# SCH_The-Weather-Station_2024-05-15.net
KiCad netlist of a schematic drawn in EasyEDA
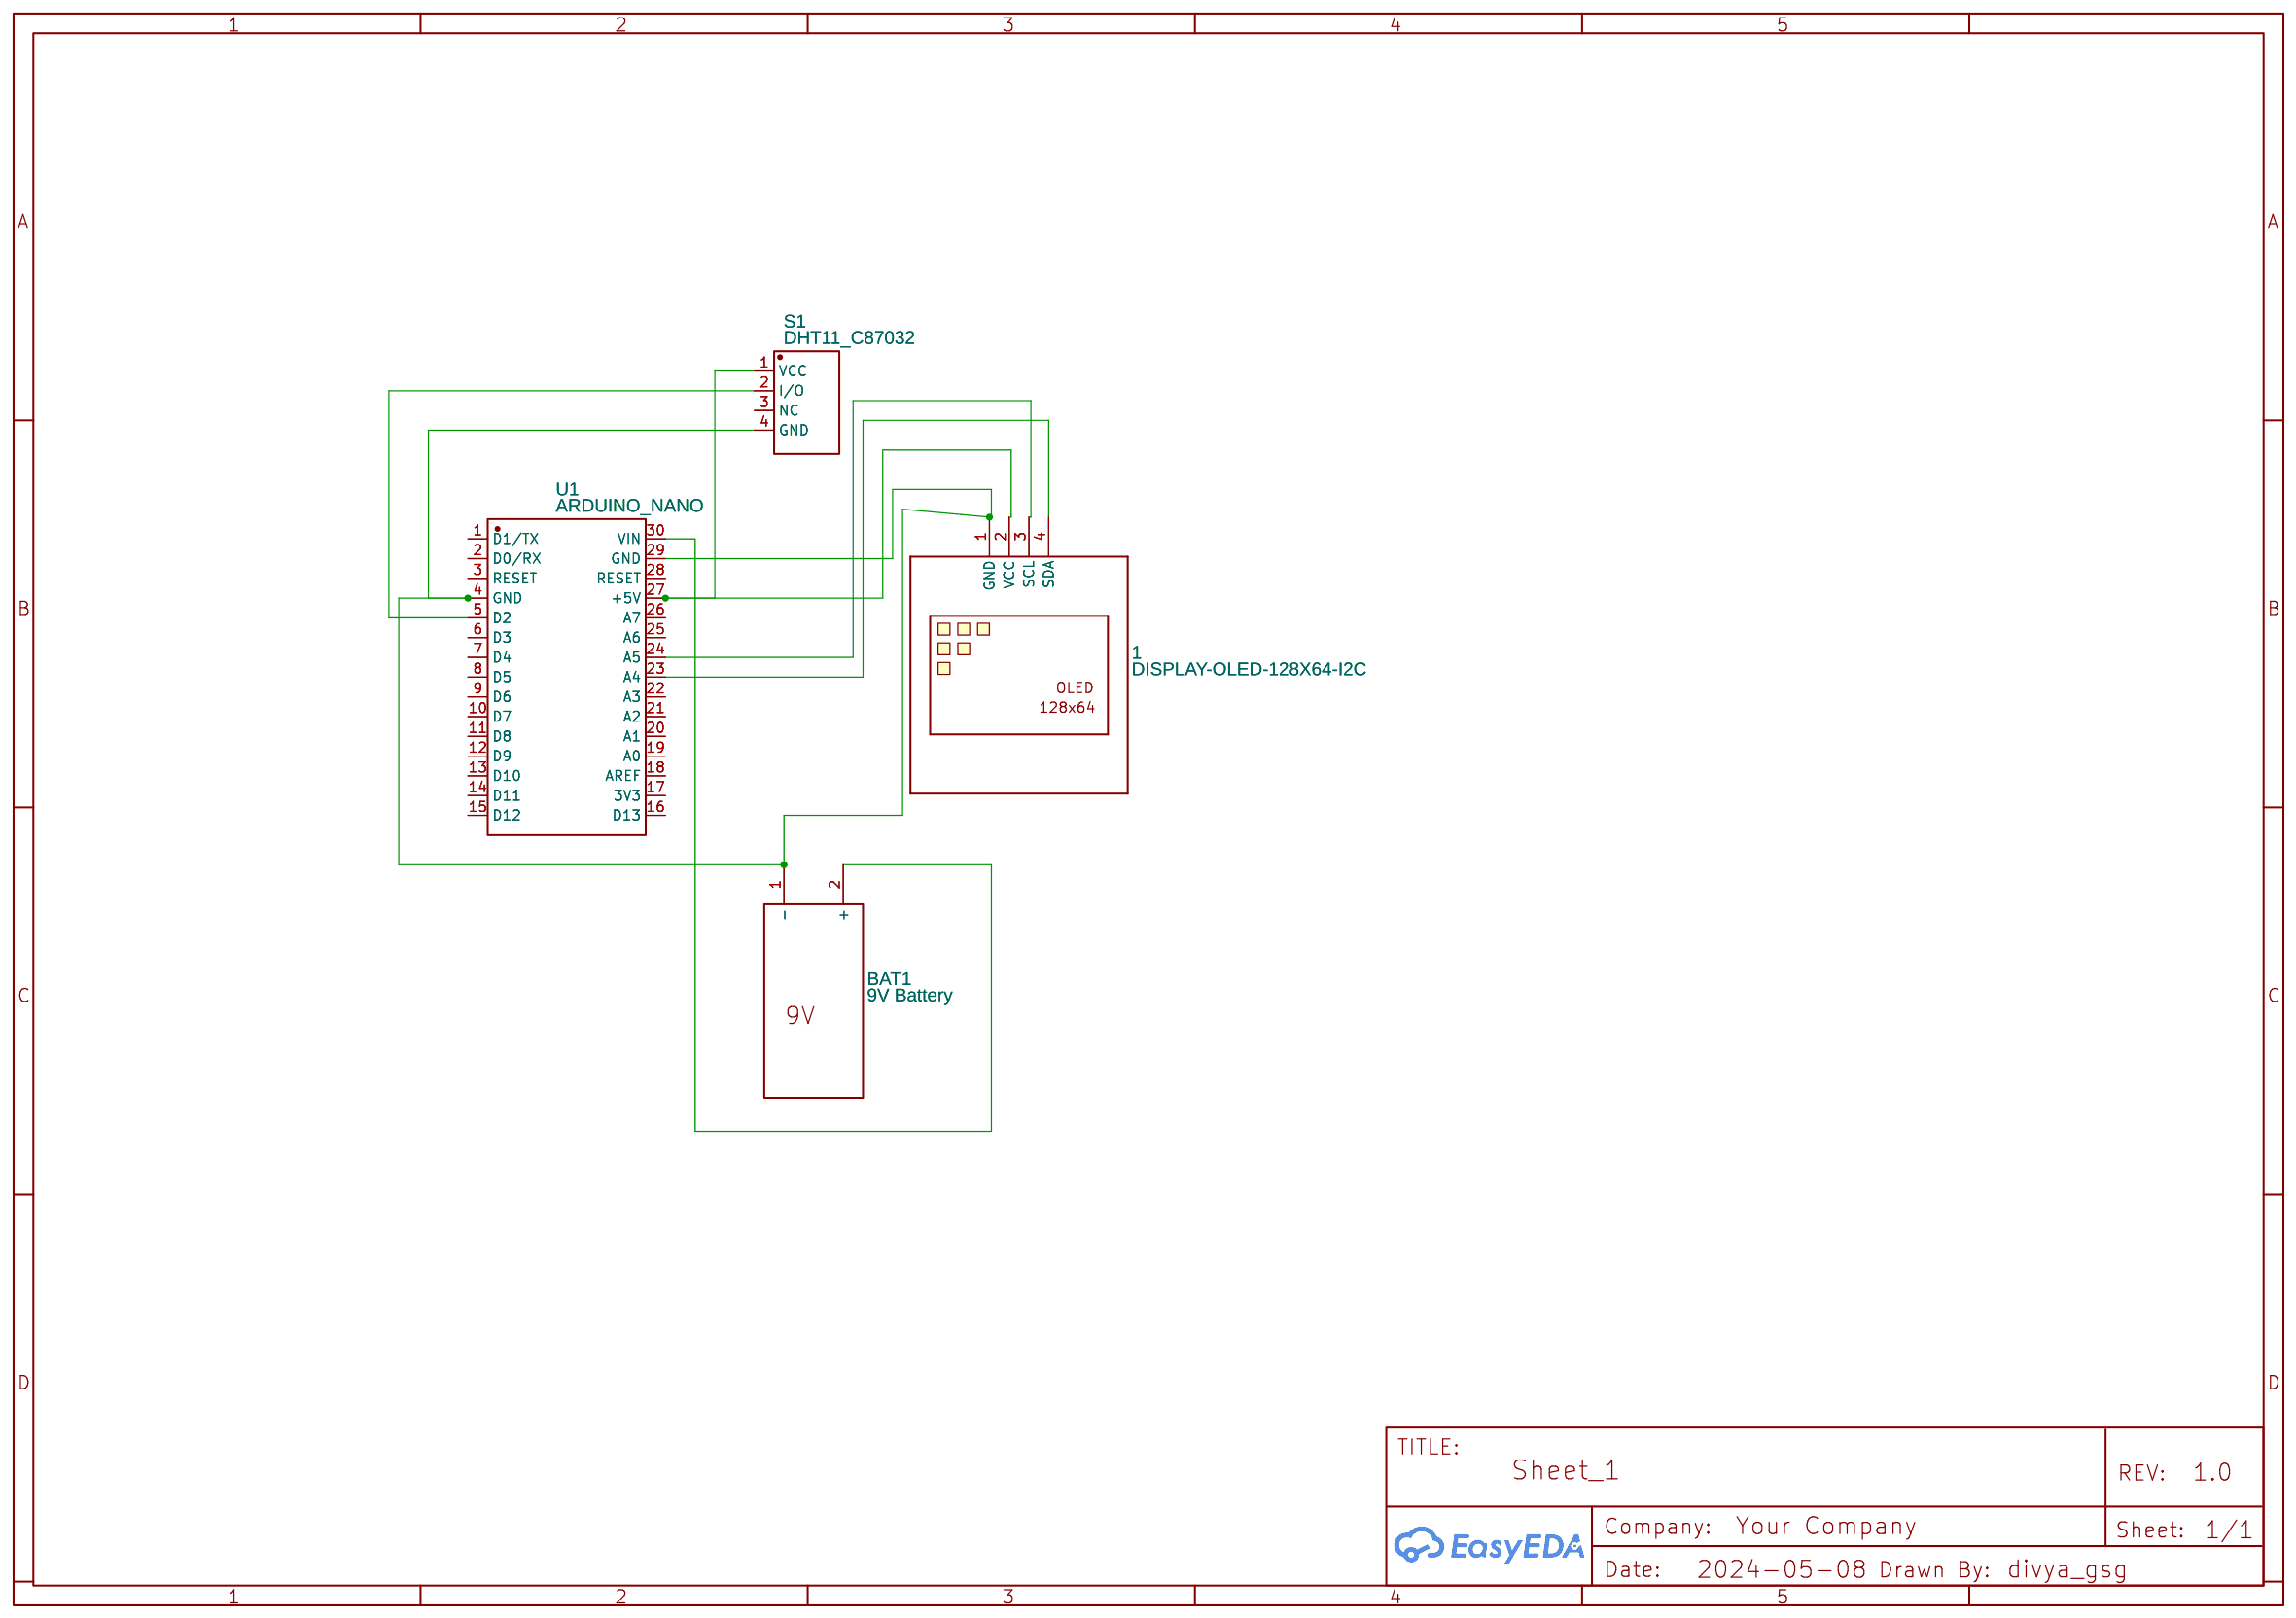
[diagram p0: schematic sheet]

(export (version "E")
  (design (tool "Eeschema 10.0.6"))
  (components
    (comp (ref "1") (value "DISPLAY-OLED-128X64-I2C") (libsource (lib "") (part "DISPLAY-OLED-128X64-I2C")))
    (comp (ref "BAT1") (value "9V Battery") (libsource (lib "") (part "9V Battery")))
    (comp (ref "S1")
      (value "DHT11_C87032")
      (fields (field (name "Manufacturer Part") "DHT11") (field (name "Manufacturer") "AOSONG"))
      (libsource (lib "") (part "DHT11_C87032"))
    )
    (comp (ref "U1") (value "ARDUINO_NANO") (libsource (lib "") (part "ARDUINO_NANO")))
  )
  (nets
    (net (code "1") (name "Net-(1-GND)") (class "Default")
      (node (ref "1") (pin "1") (pinfunction "GND_1") (pintype "bidirectional"))
      (node (ref "BAT1") (pin "1") (pinfunction "-_1") (pintype "unspecified"))
      (node (ref "S1") (pin "4") (pinfunction "GND_4") (pintype "unspecified"))
      (node (ref "U1") (pin "29") (pinfunction "GND_29") (pintype "unspecified"))
      (node (ref "U1") (pin "4") (pinfunction "GND_4") (pintype "unspecified"))
    )
    (net (code "2") (name "Net-(1-SCL)") (class "Default")
      (node (ref "1") (pin "3") (pinfunction "SCL_3") (pintype "bidirectional"))
      (node (ref "U1") (pin "24") (pinfunction "A5_24") (pintype "unspecified"))
    )
    (net (code "3") (name "Net-(1-SDA)") (class "Default")
      (node (ref "1") (pin "4") (pinfunction "SDA_4") (pintype "bidirectional"))
      (node (ref "U1") (pin "23") (pinfunction "A4_23") (pintype "unspecified"))
    )
    (net (code "4") (name "Net-(1-VCC)") (class "Default")
      (node (ref "1") (pin "2") (pinfunction "VCC_2") (pintype "bidirectional"))
      (node (ref "S1") (pin "1") (pinfunction "VCC_1") (pintype "unspecified"))
      (node (ref "U1") (pin "27") (pinfunction "+5V_27") (pintype "unspecified"))
    )
    (net (code "5") (name "Net-(BAT1-+)") (class "Default")
      (node (ref "BAT1") (pin "2") (pinfunction "+_2") (pintype "unspecified"))
      (node (ref "U1") (pin "30") (pinfunction "VIN_30") (pintype "unspecified"))
    )
    (net (code "6") (name "Net-(S1-I{slash}O)") (class "Default")
      (node (ref "S1") (pin "2") (pinfunction "I/O_2") (pintype "unspecified"))
      (node (ref "U1") (pin "5") (pinfunction "D2_5") (pintype "unspecified"))
    )
    (net (code "7") (name "unconnected-(S1-NC-Pad3)") (class "Default")
      (node (ref "S1") (pin "3") (pinfunction "NC_3") (pintype "unspecified"))
    )
    (net (code "8") (name "unconnected-(U1-3V3-Pad17)") (class "Default")
      (node (ref "U1") (pin "17") (pinfunction "3V3_17") (pintype "unspecified"))
    )
    (net (code "9") (name "unconnected-(U1-A0-Pad19)") (class "Default")
      (node (ref "U1") (pin "19") (pinfunction "A0_19") (pintype "unspecified"))
    )
    (net (code "10") (name "unconnected-(U1-A1-Pad20)") (class "Default")
      (node (ref "U1") (pin "20") (pinfunction "A1_20") (pintype "unspecified"))
    )
    (net (code "11") (name "unconnected-(U1-A2-Pad21)") (class "Default")
      (node (ref "U1") (pin "21") (pinfunction "A2_21") (pintype "unspecified"))
    )
    (net (code "12") (name "unconnected-(U1-A3-Pad22)") (class "Default")
      (node (ref "U1") (pin "22") (pinfunction "A3_22") (pintype "unspecified"))
    )
    (net (code "13") (name "unconnected-(U1-A6-Pad25)") (class "Default")
      (node (ref "U1") (pin "25") (pinfunction "A6_25") (pintype "unspecified"))
    )
    (net (code "14") (name "unconnected-(U1-A7-Pad26)") (class "Default")
      (node (ref "U1") (pin "26") (pinfunction "A7_26") (pintype "unspecified"))
    )
    (net (code "15") (name "unconnected-(U1-AREF-Pad18)") (class "Default")
      (node (ref "U1") (pin "18") (pinfunction "AREF_18") (pintype "unspecified"))
    )
    (net (code "16") (name "unconnected-(U1-D0{slash}RX-Pad2)") (class "Default")
      (node (ref "U1") (pin "2") (pinfunction "D0/RX_2") (pintype "unspecified"))
    )
    (net (code "17") (name "unconnected-(U1-D1{slash}TX-Pad1)") (class "Default")
      (node (ref "U1") (pin "1") (pinfunction "D1/TX_1") (pintype "unspecified"))
    )
    (net (code "18") (name "unconnected-(U1-D3-Pad6)") (class "Default")
      (node (ref "U1") (pin "6") (pinfunction "D3_6") (pintype "unspecified"))
    )
    (net (code "19") (name "unconnected-(U1-D4-Pad7)") (class "Default")
      (node (ref "U1") (pin "7") (pinfunction "D4_7") (pintype "unspecified"))
    )
    (net (code "20") (name "unconnected-(U1-D5-Pad8)") (class "Default")
      (node (ref "U1") (pin "8") (pinfunction "D5_8") (pintype "unspecified"))
    )
    (net (code "21") (name "unconnected-(U1-D6-Pad9)") (class "Default")
      (node (ref "U1") (pin "9") (pinfunction "D6_9") (pintype "unspecified"))
    )
    (net (code "22") (name "unconnected-(U1-D7-Pad10)") (class "Default")
      (node (ref "U1") (pin "10") (pinfunction "D7_10") (pintype "unspecified"))
    )
    (net (code "23") (name "unconnected-(U1-D8-Pad11)") (class "Default")
      (node (ref "U1") (pin "11") (pinfunction "D8_11") (pintype "unspecified"))
    )
    (net (code "24") (name "unconnected-(U1-D9-Pad12)") (class "Default")
      (node (ref "U1") (pin "12") (pinfunction "D9_12") (pintype "unspecified"))
    )
    (net (code "25") (name "unconnected-(U1-D10-Pad13)") (class "Default")
      (node (ref "U1") (pin "13") (pinfunction "D10_13") (pintype "unspecified"))
    )
    (net (code "26") (name "unconnected-(U1-D11-Pad14)") (class "Default")
      (node (ref "U1") (pin "14") (pinfunction "D11_14") (pintype "unspecified"))
    )
    (net (code "27") (name "unconnected-(U1-D12-Pad15)") (class "Default")
      (node (ref "U1") (pin "15") (pinfunction "D12_15") (pintype "unspecified"))
    )
    (net (code "28") (name "unconnected-(U1-D13-Pad16)") (class "Default")
      (node (ref "U1") (pin "16") (pinfunction "D13_16") (pintype "unspecified"))
    )
    (net (code "29") (name "unconnected-(U1-RESET-Pad3)") (class "Default")
      (node (ref "U1") (pin "3") (pinfunction "RESET_3") (pintype "unspecified"))
    )
    (net (code "30") (name "unconnected-(U1-RESET-Pad28)") (class "Default")
      (node (ref "U1") (pin "28") (pinfunction "RESET_28") (pintype "unspecified"))
    )
  )
)
